# Power_Sleep_Timer.net
KiCad netlist of a schematic drawn in Altium Designer
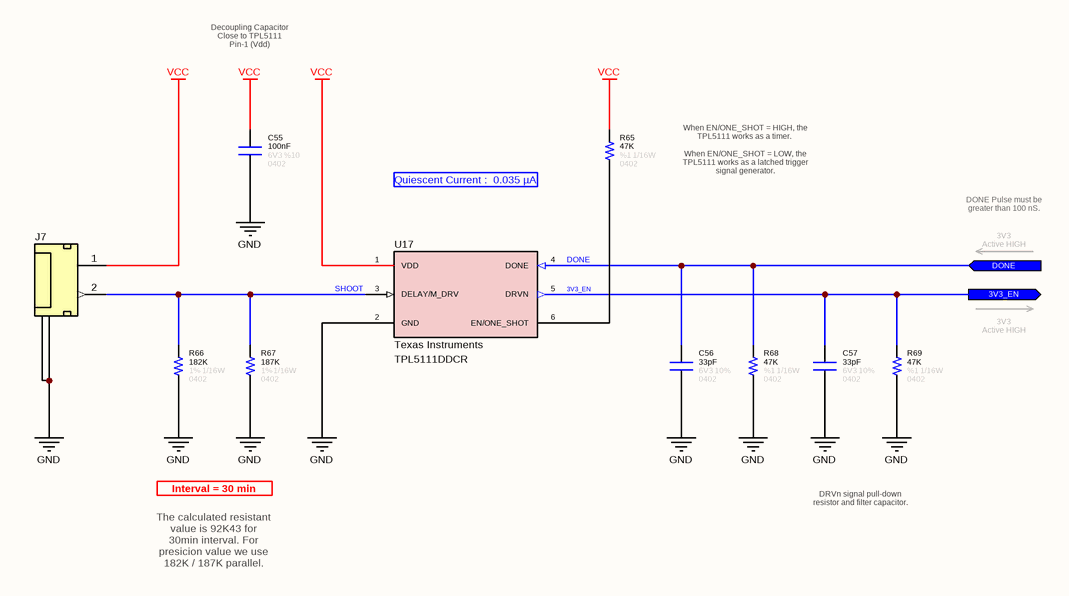
[diagram p0: Power Sleep Timer.SchDoc]

(export (version "E")
  (design (tool "Eeschema 10.0.6"))
  (components
    (comp (ref "C55")
      (value "100nF")
      (footprint "CAPACITOR_0402")
      (description "Capacitor - 100nF [0402-6V3] (Ceramic)")
      (fields
        (field (name "MANUFACTURER PART NUMBER") "04026D104KAT4A")
        (field (name "TOLERANCE") "%10")
        (field (name "VOLTAGE") "6V3")
        (field (name "CASE") "0402")
        (field (name "Comment") "Capacitor - 100nF [0402] (Ceramic)")
      )
      (libsource (lib "Akkoyun") (part "Capacitor - 100nF [0402-6V3]"))
    )
    (comp (ref "C56")
      (value "33pF")
      (footprint "CAPACITOR_0402")
      (description "Capacitor - 33pF [0402] (Ceramic)")
      (fields
        (field (name "MANUFACTURER PART NUMBER") "C0402C330J9RACAUTO")
        (field (name "TOLERANCE") "10%")
        (field (name "CASE") "0402")
        (field (name "VOLTAGE") "6V3")
      )
      (libsource (lib "Akkoyun") (part "Capacitor - 33pF [0402-6V3]"))
    )
    (comp (ref "C57")
      (value "33pF")
      (footprint "CAPACITOR_0402")
      (description "Capacitor - 33pF [0402] (Ceramic)")
      (fields
        (field (name "MANUFACTURER PART NUMBER") "C0402C330J9RACAUTO")
        (field (name "TOLERANCE") "10%")
        (field (name "CASE") "0402")
        (field (name "VOLTAGE") "6V3")
      )
      (libsource (lib "Akkoyun") (part "Capacitor - 33pF [0402-6V3]"))
    )
    (comp (ref "J7")
      (value "2P SMD Tunic Connector")
      (footprint "Connector_Tunic 2P")
      (description "Mini Tunic Connector with 2P")
      (fields
        (field (name "MANUFACTURER PART NUMBER") "53261-0271")
        (field (name "MOUSER PART NUMBER") "538-53261-0271")
      )
      (libsource (lib "Akkoyun") (part "Connector - Mini Tunic 2P (1.25)"))
    )
    (comp (ref "R65")
      (value "47K")
      (footprint "RESISTOR_0402")
      (description "Thick Film Resistors - SMD 1/16 W 47 KOhm 1%")
      (fields
        (field (name "MANUFACTURER PART NUMBER") "CRCW040247K0FKED")
        (field (name "TOLERANCE") "%1")
        (field (name "CASE") "0402")
        (field (name "POWER") "1/16W")
        (field (name "Comment") "47K - 0402 - %1 - 1/16W")
      )
      (libsource (lib "Akkoyun") (part "Resistor - 47K [0402]"))
    )
    (comp (ref "R66")
      (value "182K")
      (footprint "RESISTOR_0402")
      (description "Thick Film Resistors - SMD 1/16 W 182 KOhm 1%")
      (fields
        (field (name "MANUFACTURER PART NUMBER") "CRCW0402182KFKEDC")
        (field (name "POWER") "1/16W")
        (field (name "CASE") "0402")
        (field (name "TOLERANCE") "1%")
        (field (name "Comment") "182K - 0402 - %1 - 1/16W")
      )
      (libsource (lib "Akkoyun") (part "Resistor - 182K [0402]"))
    )
    (comp (ref "R67")
      (value "187K")
      (footprint "RESISTOR_0402")
      (description "Thick Film Resistors - SMD 1/16 W 187 KOhm 1%")
      (fields
        (field (name "MANUFACTURER PART NUMBER") "CRCW0402182KFKEDC")
        (field (name "POWER") "1/16W")
        (field (name "CASE") "0402")
        (field (name "TOLERANCE") "1%")
        (field (name "Comment") "187K - 0402 - %1 - 1/16W")
      )
      (libsource (lib "Akkoyun") (part "Resistor - 187K [0402]"))
    )
    (comp (ref "R68")
      (value "47K")
      (footprint "RESISTOR_0402")
      (description "Thick Film Resistors - SMD 1/16 W 47 KOhm 1%")
      (fields
        (field (name "MANUFACTURER PART NUMBER") "CRCW040247K0FKED")
        (field (name "TOLERANCE") "%1")
        (field (name "CASE") "0402")
        (field (name "POWER") "1/16W")
        (field (name "Comment") "47K - 0402 - %1 - 1/16W")
      )
      (libsource (lib "Akkoyun") (part "Resistor - 47K [0402]"))
    )
    (comp (ref "R69")
      (value "47K")
      (footprint "RESISTOR_0402")
      (description "Thick Film Resistors - SMD 1/16 W 47 KOhm 1%")
      (fields
        (field (name "MANUFACTURER PART NUMBER") "CRCW040247K0FKED")
        (field (name "TOLERANCE") "%1")
        (field (name "CASE") "0402")
        (field (name "POWER") "1/16W")
        (field (name "Comment") "47K - 0402 - %1 - 1/16W")
      )
      (libsource (lib "Akkoyun") (part "Resistor - 47K [0402]"))
    )
    (comp (ref "U17")
      (value "TPL5111DDCR")
      (footprint "SOT-23-6")
      (description "NANO-POWER SYSTEM TIMER FOR POWE")
      (fields
        (field (name "MANUFACTURER NAME") "Texas Instruments")
        (field (name "MANUFACTURER PART NUMBER") "TPL5111DDCR")
      )
      (libsource (lib "Akkoyun") (part "IC - TPL5111"))
    )
  )
  (nets
    (net (code "1") (name "/3V3_EN") (class "Default")
      (node (ref "C57") (pin "2") (pinfunction "2_2") (pintype "passive"))
      (node (ref "R69") (pin "2") (pinfunction "2_2") (pintype "passive"))
      (node (ref "U17") (pin "5") (pinfunction "DRVN_5") (pintype "output"))
    )
    (net (code "2") (name "/DONE") (class "Default")
      (node (ref "C56") (pin "2") (pinfunction "2_2") (pintype "passive"))
      (node (ref "R68") (pin "2") (pinfunction "2_2") (pintype "passive"))
      (node (ref "U17") (pin "4") (pinfunction "DONE_4") (pintype "input"))
    )
    (net (code "3") (name "/SHOOT") (class "Default")
      (node (ref "J7") (pin "2") (pinfunction "Pin2_2") (pintype "output"))
      (node (ref "R66") (pin "2") (pinfunction "2_2") (pintype "passive"))
      (node (ref "R67") (pin "2") (pinfunction "2_2") (pintype "passive"))
      (node (ref "U17") (pin "3") (pinfunction "DELAY/M_DRV_3") (pintype "input"))
    )
    (net (code "4") (name "GND") (class "Default")
      (node (ref "C55") (pin "1") (pinfunction "1_1") (pintype "passive"))
      (node (ref "C56") (pin "1") (pinfunction "1_1") (pintype "passive"))
      (node (ref "C57") (pin "1") (pinfunction "1_1") (pintype "passive"))
      (node (ref "J7") (pin "3") (pinfunction "GND_3") (pintype "passive"))
      (node (ref "J7") (pin "4") (pinfunction "GND_4") (pintype "passive"))
      (node (ref "R66") (pin "1") (pinfunction "1_1") (pintype "passive"))
      (node (ref "R67") (pin "1") (pinfunction "1_1") (pintype "passive"))
      (node (ref "R68") (pin "1") (pinfunction "1_1") (pintype "passive"))
      (node (ref "R69") (pin "1") (pinfunction "1_1") (pintype "passive"))
      (node (ref "U17") (pin "2") (pinfunction "GND_2") (pintype "power_in"))
    )
    (net (code "5") (name "Net-(U17-EN{slash}ONE_SHOT)") (class "Default")
      (node (ref "R65") (pin "1") (pinfunction "1_1") (pintype "passive"))
      (node (ref "U17") (pin "6") (pinfunction "EN/ONE_SHOT_6") (pintype "passive"))
    )
    (net (code "6") (name "VCC") (class "Default")
      (node (ref "C55") (pin "2") (pinfunction "2_2") (pintype "passive"))
      (node (ref "J7") (pin "1") (pinfunction "Pin1_1") (pintype "power_in"))
      (node (ref "R65") (pin "2") (pinfunction "2_2") (pintype "passive"))
      (node (ref "U17") (pin "1") (pinfunction "VDD_1") (pintype "power_in"))
    )
  )
)
